# CONNECTOR.net
KiCad netlist of a schematic drawn in Altium Designer
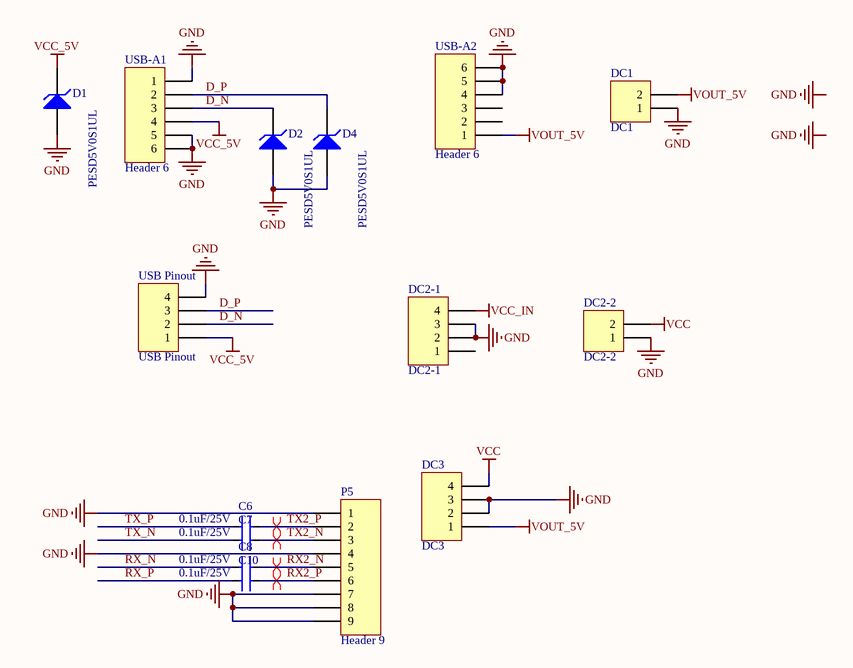
[diagram p0: CONNECTOR.SchDoc]

(export (version "E")
  (design (tool "Eeschema 10.0.6"))
  (components
    (comp (ref "C6")
      (value "0.1uF/25V")
      (footprint "0603C")
      (description "CCX85-103")
      (libsource (lib "无极性电容") (part "0.01UF"))
    )
    (comp (ref "C7")
      (value "0.1uF/25V")
      (footprint "0603C")
      (description "CCX85-103")
      (libsource (lib "无极性电容") (part "0.01UF"))
    )
    (comp (ref "C8")
      (value "0.1uF/25V")
      (footprint "0603C")
      (description "CCX85-103")
      (libsource (lib "无极性电容") (part "0.01UF"))
    )
    (comp (ref "C10")
      (value "0.1uF/25V")
      (footprint "0603C")
      (description "CCX85-103")
      (libsource (lib "无极性电容") (part "0.01UF"))
    )
    (comp (ref "D1")
      (value "PESD5V0S1UL")
      (footprint "0402R")
      (description "Zener Diode")
      (fields (field (name "PUBLISHER") "Altium Limited"))
      (libsource (lib "Miscellaneous Devices") (part "D Zener"))
    )
    (comp (ref "D2")
      (value "PESD5V0S1UL")
      (footprint "0402R")
      (description "Zener Diode")
      (fields (field (name "PUBLISHER") "Altium Limited"))
      (libsource (lib "Miscellaneous Devices") (part "D Zener"))
    )
    (comp (ref "D4")
      (value "PESD5V0S1UL")
      (footprint "0402R")
      (description "Zener Diode")
      (fields (field (name "PUBLISHER") "Altium Limited"))
      (libsource (lib "Miscellaneous Devices") (part "D Zener"))
    )
    (comp (ref "DC1")
      (value "DC1")
      (footprint "2X2MMZ")
      (description "Header, 2-Pin")
      (fields (field (name "PUBLISHER") "Altium Limited"))
      (libsource (lib "Miscellaneous Connectors") (part "Header 2"))
    )
    (comp (ref "DC2-1")
      (value "DC2-1")
      (footprint "DC005")
      (description "Header, 4-Pin")
      (fields (field (name "PUBLISHER") "Altium Limited"))
      (libsource (lib "Miscellaneous Connectors") (part "Header 4"))
    )
    (comp (ref "DC2-2")
      (value "DC2-2")
      (footprint "2X2MMZ")
      (description "Header, 2-Pin")
      (fields (field (name "PUBLISHER") "Altium Limited"))
      (libsource (lib "Miscellaneous Connectors") (part "Header 2"))
    )
    (comp (ref "DC3")
      (value "DC3")
      (footprint "2X4MMZ")
      (description "Header, 4-Pin")
      (fields (field (name "PUBLISHER") "Altium Limited"))
      (libsource (lib "Miscellaneous Connectors") (part "Header 4"))
    )
    (comp (ref "P5")
      (value "Header 9")
      (footprint "SATA 7P")
      (description "Header, 9-Pin")
      (fields (field (name "PUBLISHER") "Altium Limited"))
      (libsource (lib "Miscellaneous Connectors") (part "Header 9"))
    )
    (comp (ref "USB Pinout")
      (value "USB Pinout")
      (footprint "sip-4l")
      (description "Header, 4-Pin")
      (fields (field (name "PUBLISHER") "Altium Limited"))
      (libsource (lib "Miscellaneous Connectors") (part "Header 4"))
    )
    (comp (ref "USB-A1")
      (value "Header 6")
      (footprint "USB-A-C")
      (description "Header, 6-Pin")
      (fields (field (name "PUBLISHER") "Altium Limited"))
      (libsource (lib "Miscellaneous Connectors") (part "Header 6"))
    )
    (comp (ref "USB-A2")
      (value "Header 6")
      (footprint "USB-A-C")
      (description "Header, 6-Pin")
      (fields (field (name "PUBLISHER") "Altium Limited"))
      (libsource (lib "") (part "Header 6_1"))
    )
  )
  (nets
    (net (code "1") (name "/D_N") (class "Default")
      (node (ref "D2") (pin "2") (pinfunction "K_2") (pintype "passive"))
      (node (ref "USB Pinout") (pin "2") (pinfunction "2_2") (pintype "passive"))
      (node (ref "USB-A1") (pin "3") (pinfunction "3_3") (pintype "passive"))
    )
    (net (code "2") (name "/D_P") (class "Default")
      (node (ref "D4") (pin "2") (pinfunction "K_2") (pintype "passive"))
      (node (ref "USB Pinout") (pin "3") (pinfunction "3_3") (pintype "passive"))
      (node (ref "USB-A1") (pin "2") (pinfunction "2_2") (pintype "passive"))
    )
    (net (code "3") (name "/RX2_N") (class "Default")
      (node (ref "C8") (pin "2") (pinfunction "2_2") (pintype "passive"))
      (node (ref "P5") (pin "5") (pinfunction "5_5") (pintype "passive"))
    )
    (net (code "4") (name "/RX2_P") (class "Default")
      (node (ref "C10") (pin "2") (pinfunction "2_2") (pintype "passive"))
      (node (ref "P5") (pin "6") (pinfunction "6_6") (pintype "passive"))
    )
    (net (code "5") (name "/RX_N") (class "Default")
      (node (ref "C8") (pin "1") (pinfunction "1_1") (pintype "passive"))
    )
    (net (code "6") (name "/RX_P") (class "Default")
      (node (ref "C10") (pin "1") (pinfunction "1_1") (pintype "passive"))
    )
    (net (code "7") (name "/TX2_N") (class "Default")
      (node (ref "C7") (pin "2") (pinfunction "2_2") (pintype "passive"))
      (node (ref "P5") (pin "3") (pinfunction "3_3") (pintype "passive"))
    )
    (net (code "8") (name "/TX2_P") (class "Default")
      (node (ref "C6") (pin "2") (pinfunction "2_2") (pintype "passive"))
      (node (ref "P5") (pin "2") (pinfunction "2_2") (pintype "passive"))
    )
    (net (code "9") (name "/TX_N") (class "Default")
      (node (ref "C7") (pin "1") (pinfunction "1_1") (pintype "passive"))
    )
    (net (code "10") (name "/TX_P") (class "Default")
      (node (ref "C6") (pin "1") (pinfunction "1_1") (pintype "passive"))
    )
    (net (code "11") (name "GND") (class "Default")
      (node (ref "D1") (pin "1") (pinfunction "A_1") (pintype "passive"))
      (node (ref "D2") (pin "1") (pinfunction "A_1") (pintype "passive"))
      (node (ref "D4") (pin "1") (pinfunction "A_1") (pintype "passive"))
      (node (ref "DC1") (pin "1") (pinfunction "1_1") (pintype "passive"))
      (node (ref "DC2-1") (pin "2") (pinfunction "2_2") (pintype "passive"))
      (node (ref "DC2-1") (pin "3") (pinfunction "3_3") (pintype "passive"))
      (node (ref "DC2-2") (pin "1") (pinfunction "1_1") (pintype "passive"))
      (node (ref "DC3") (pin "2") (pinfunction "2_2") (pintype "passive"))
      (node (ref "DC3") (pin "3") (pinfunction "3_3") (pintype "passive"))
      (node (ref "P5") (pin "1") (pinfunction "1_1") (pintype "passive"))
      (node (ref "P5") (pin "4") (pinfunction "4_4") (pintype "passive"))
      (node (ref "P5") (pin "7") (pinfunction "7_7") (pintype "passive"))
      (node (ref "P5") (pin "8") (pinfunction "8_8") (pintype "passive"))
      (node (ref "P5") (pin "9") (pinfunction "9_9") (pintype "passive"))
      (node (ref "USB Pinout") (pin "4") (pinfunction "4_4") (pintype "passive"))
      (node (ref "USB-A1") (pin "1") (pinfunction "1_1") (pintype "passive"))
      (node (ref "USB-A1") (pin "5") (pinfunction "5_5") (pintype "passive"))
      (node (ref "USB-A1") (pin "6") (pinfunction "6_6") (pintype "passive"))
      (node (ref "USB-A2") (pin "4") (pinfunction "4_4") (pintype "passive"))
      (node (ref "USB-A2") (pin "5") (pinfunction "5_5") (pintype "passive"))
      (node (ref "USB-A2") (pin "6") (pinfunction "6_6") (pintype "passive"))
    )
    (net (code "12") (name "VCC") (class "Default")
      (node (ref "DC2-2") (pin "2") (pinfunction "2_2") (pintype "passive"))
      (node (ref "DC3") (pin "4") (pinfunction "4_4") (pintype "passive"))
    )
    (net (code "13") (name "VCC_5V") (class "Default")
      (node (ref "D1") (pin "2") (pinfunction "K_2") (pintype "passive"))
      (node (ref "USB Pinout") (pin "1") (pinfunction "1_1") (pintype "passive"))
      (node (ref "USB-A1") (pin "4") (pinfunction "4_4") (pintype "passive"))
    )
    (net (code "14") (name "VCC_IN") (class "Default")
      (node (ref "DC2-1") (pin "4") (pinfunction "4_4") (pintype "passive"))
    )
    (net (code "15") (name "VOUT_5V") (class "Default")
      (node (ref "DC1") (pin "2") (pinfunction "2_2") (pintype "passive"))
      (node (ref "DC3") (pin "1") (pinfunction "1_1") (pintype "passive"))
      (node (ref "USB-A2") (pin "1") (pinfunction "1_1") (pintype "passive"))
    )
    (net (code "16") (name "unconnected-(DC2-1-Pad1)") (class "Default")
      (node (ref "DC2-1") (pin "1") (pinfunction "1_1") (pintype "passive"))
    )
    (net (code "17") (name "unconnected-(USB-A2-Pad2)") (class "Default")
      (node (ref "USB-A2") (pin "2") (pinfunction "2_2") (pintype "passive"))
    )
    (net (code "18") (name "unconnected-(USB-A2-Pad3)") (class "Default")
      (node (ref "USB-A2") (pin "3") (pinfunction "3_3") (pintype "passive"))
    )
  )
)
